# p2sdc-001.net
KiCad netlist of a schematic drawn in EAGLE
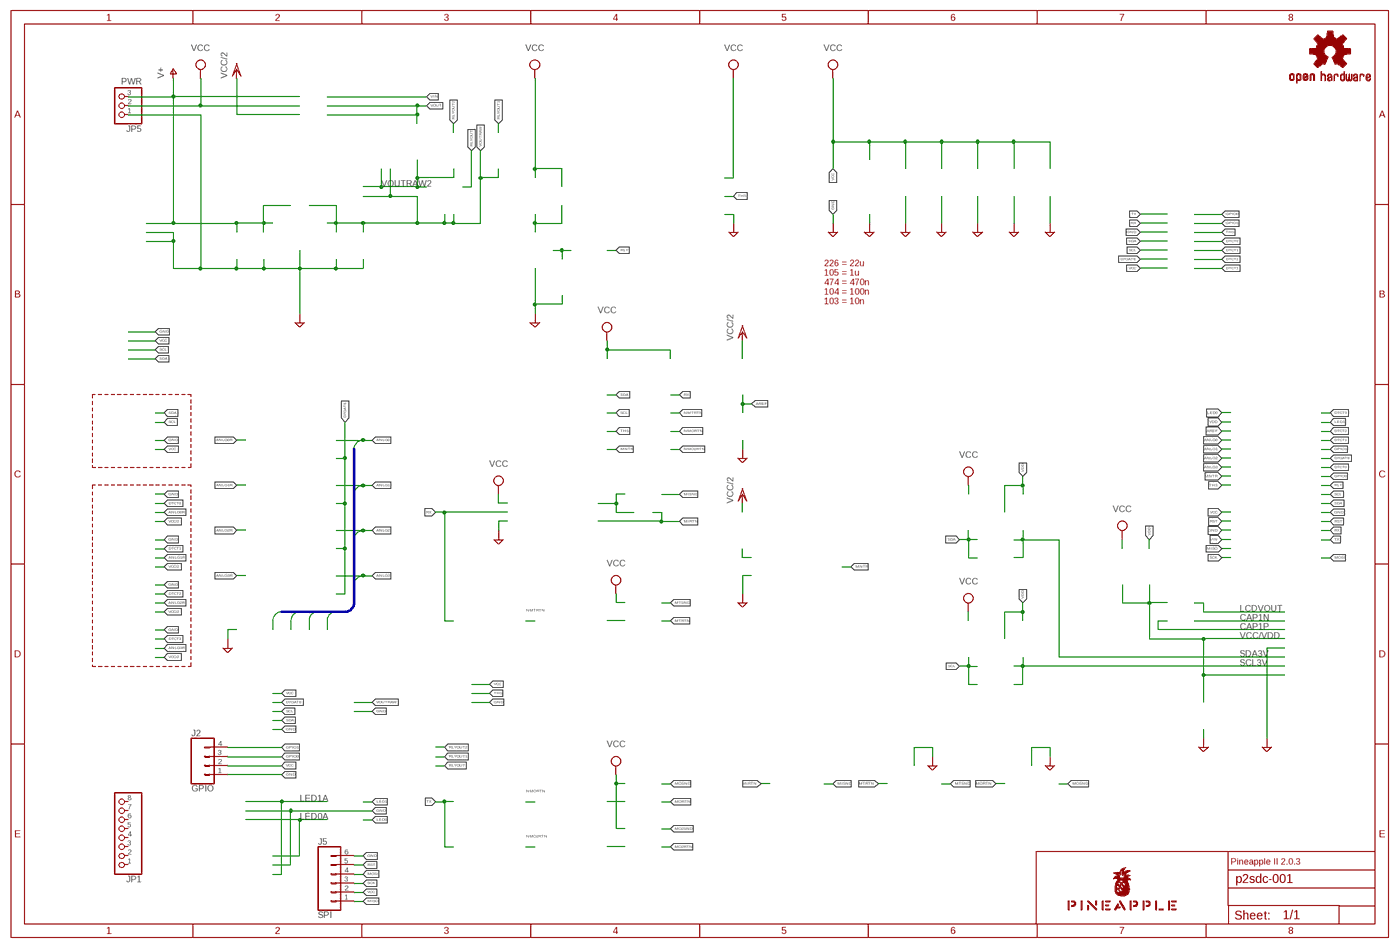
[diagram p0: schematic, sheet 1, overview]
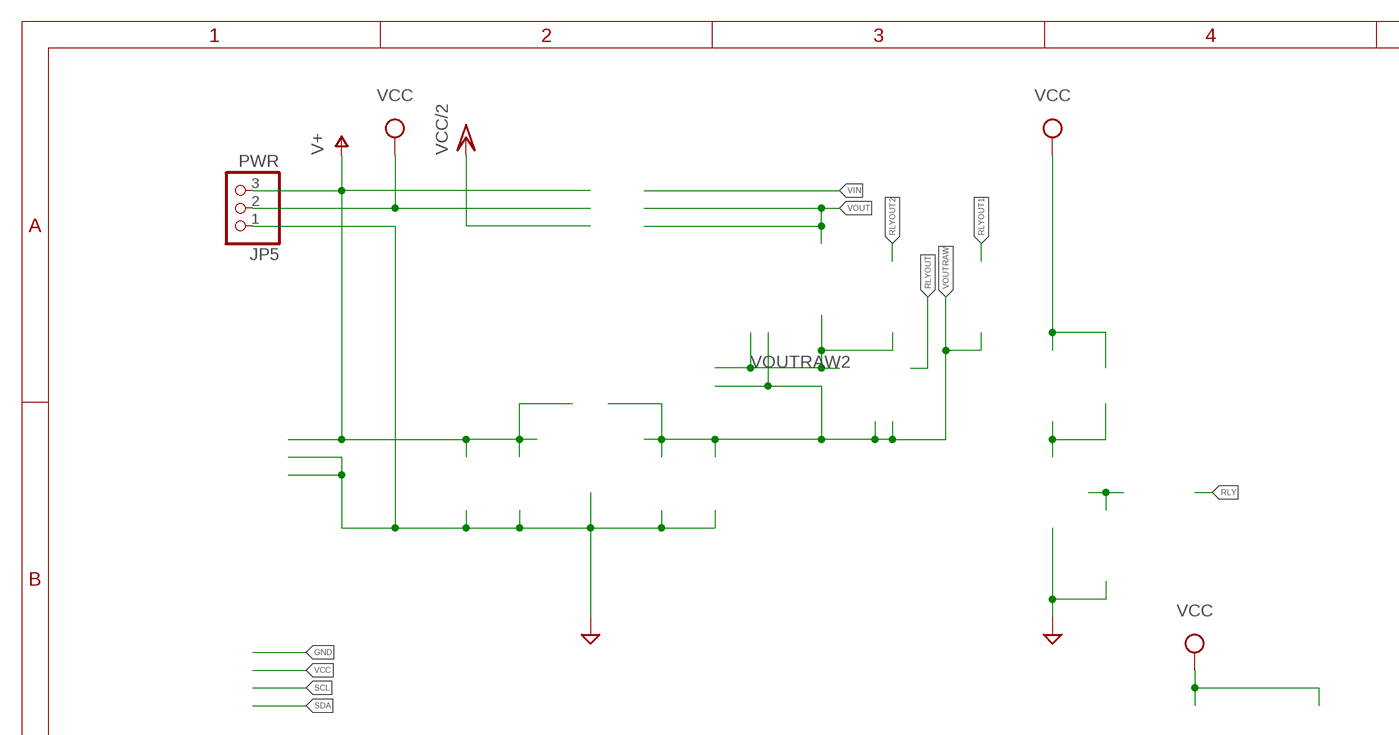
[diagram p1: schematic, sheet 1, part 1 of 4]
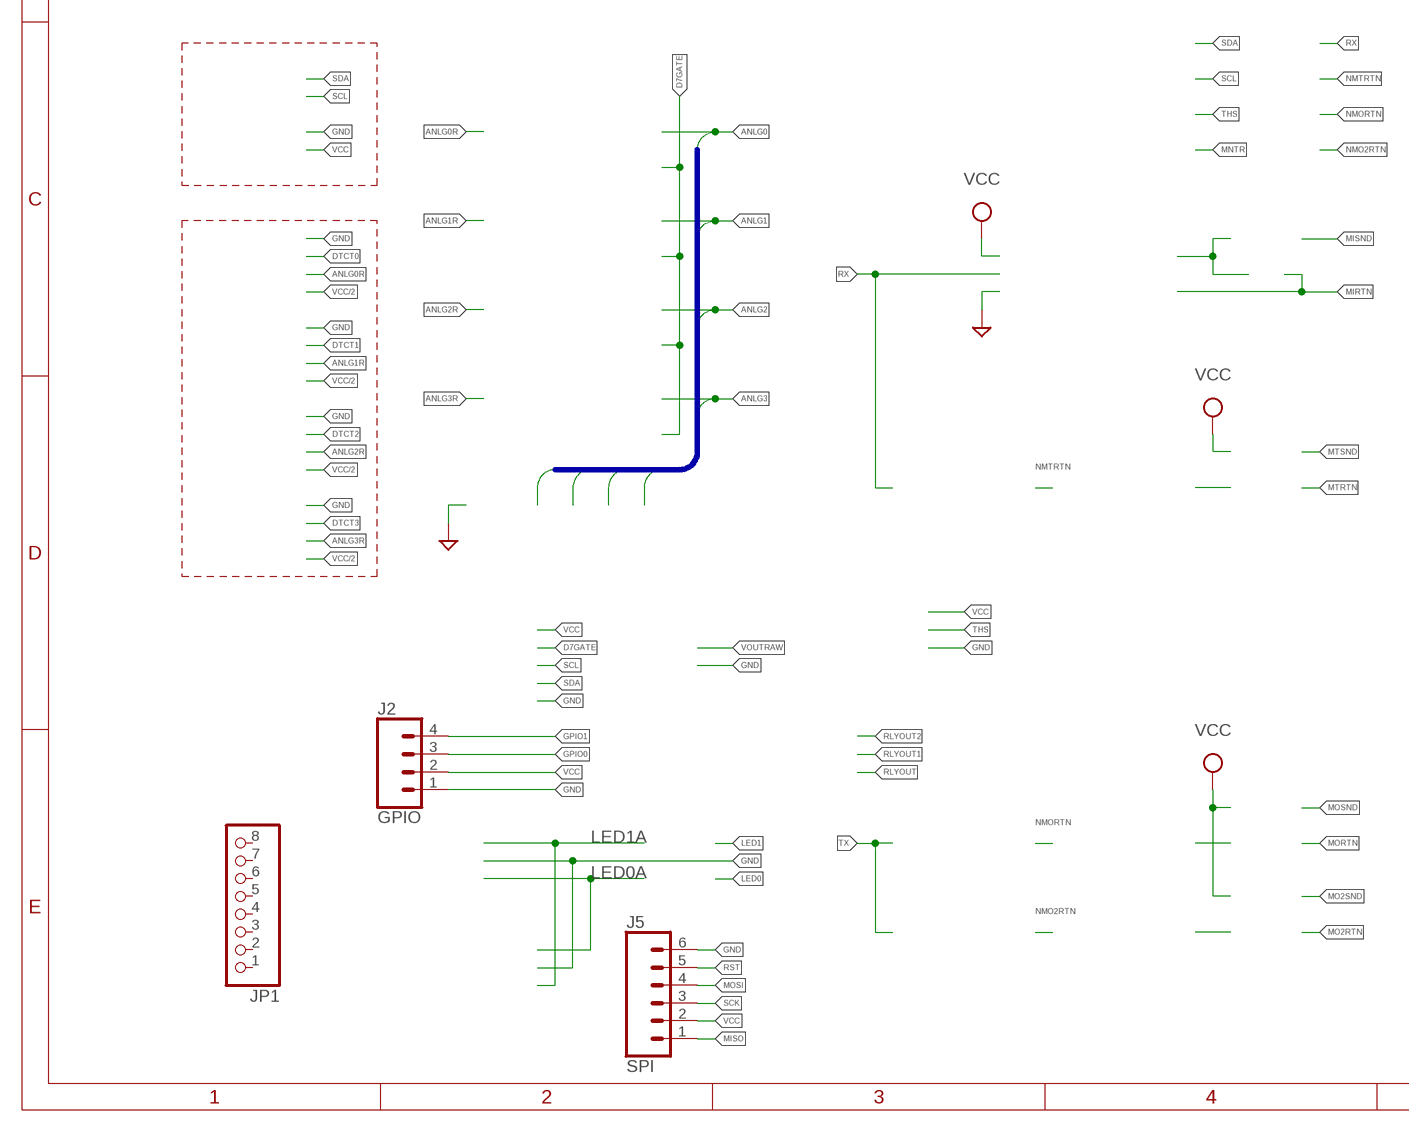
[diagram p2: schematic, sheet 1, part 2 of 4]
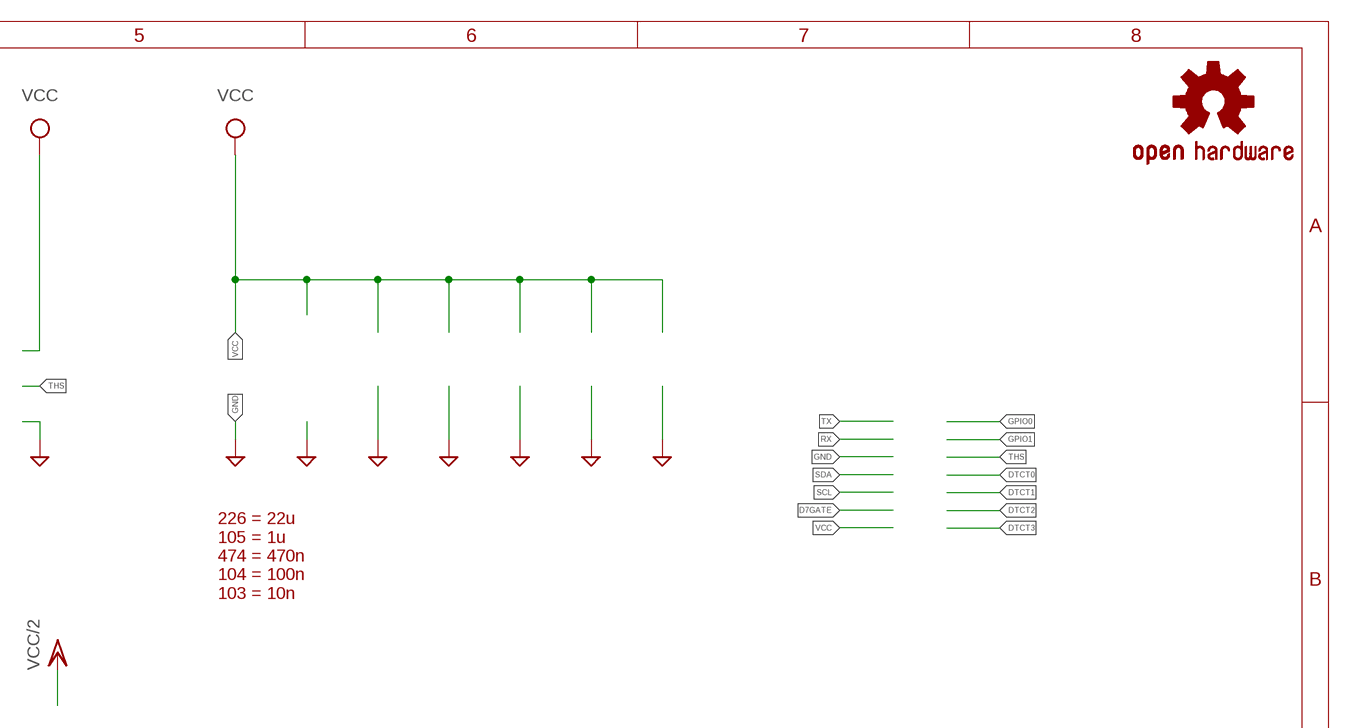
[diagram p3: schematic, sheet 1, part 3 of 4]
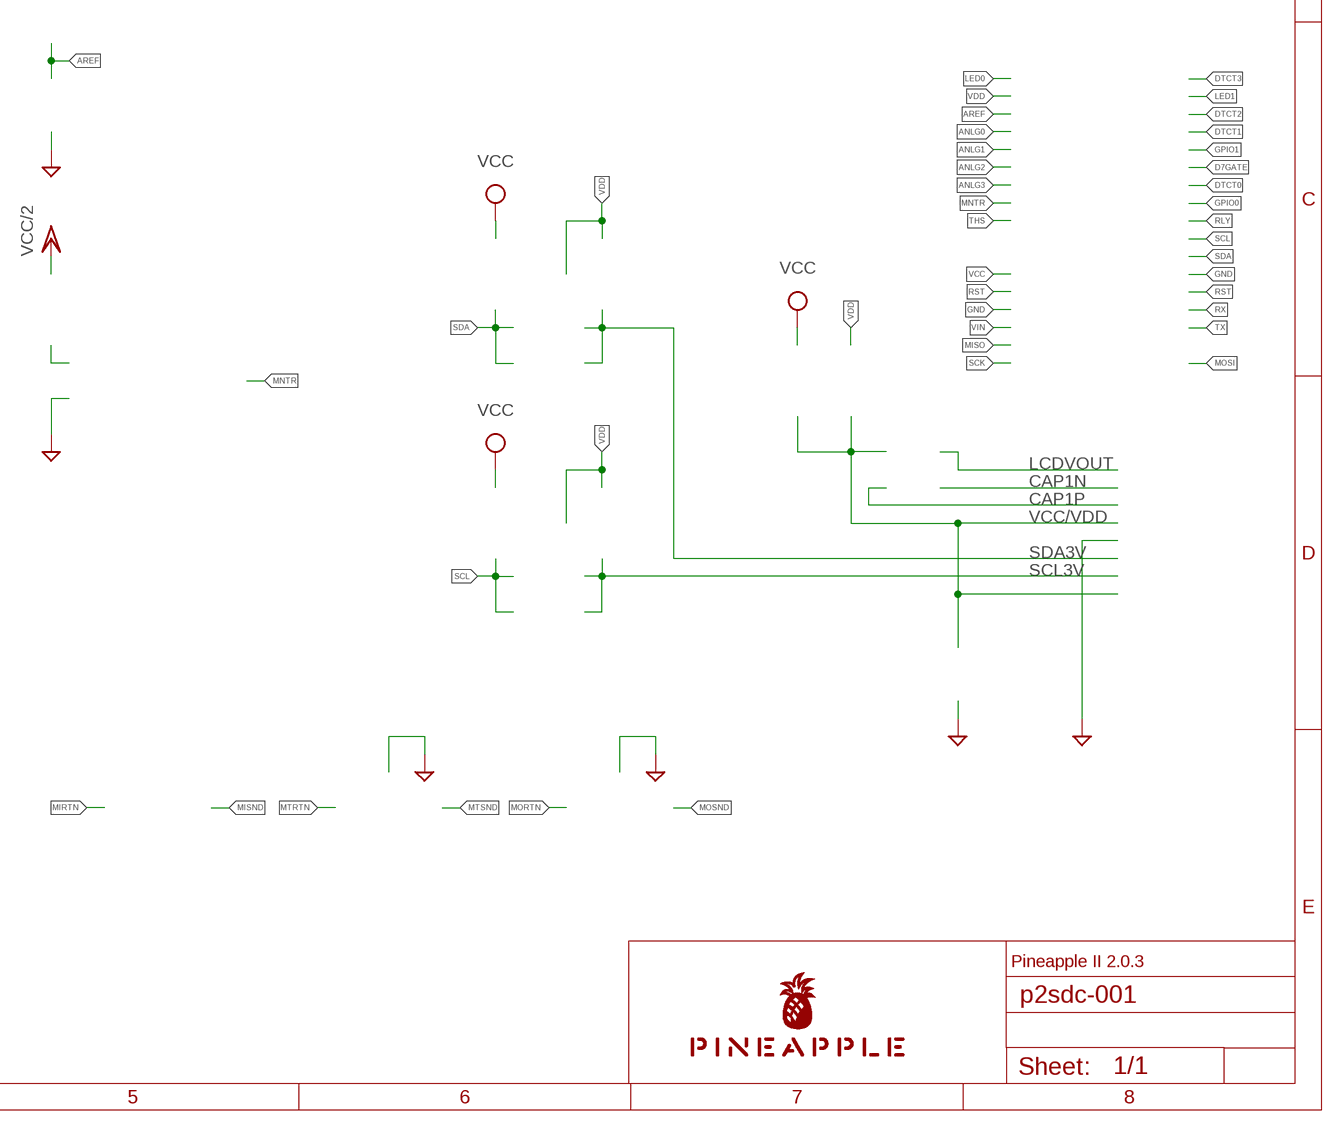
[diagram p4: schematic, sheet 1, part 4 of 4]

(export (version "E")
  (design (tool "Eeschema 10.0.6"))
  (components
    (comp (ref "J2")
      (value "GPIO")
      (footprint "eagle-import:JST-4-PTH")
      (libsource (lib "eagle-import") (part "CONN_04JST-PTH"))
    )
    (comp (ref "J5")
      (value "SPI")
      (footprint "eagle-import:1X06_1.27MM")
      (libsource (lib "eagle-import") (part "CONN_061.27MM"))
    )
    (comp (ref "JP1")
      (value "PINHD-1X8")
      (footprint "eagle-import:1X08")
      (libsource (lib "eagle-import") (part "PINHD-1X8"))
    )
    (comp (ref "JP5")
      (value "PWR")
      (footprint "eagle-import:1X03")
      (libsource (lib "eagle-import") (part "PINHD-1X3"))
    )
    (comp (ref "LOGO1")
      (value "OSHW-LOGOS-COPPER")
      (footprint "eagle-import:OSHW-LOGO-S_COPPER")
      (libsource (lib "eagle-import") (part "OSHW-LOGOS-COPPER"))
    )
    (comp (ref "U$1")
      (value "PINEAPPLE450_SILK")
      (footprint "eagle-import:PINEAPPLE450_SILK")
      (libsource (lib "eagle-import") (part "PINEAPPLE450_SILK"))
    )
  )
  (nets
    (net (code "24") (name "GND") (class "Default")
      (node (ref "J2") (pin "1") (pinfunction "1_1") (pintype "passive"))
      (node (ref "J5") (pin "6") (pinfunction "6_6") (pintype "passive"))
      (node (ref "JP5") (pin "1") (pinfunction "1_1") (pintype "passive"))
    )
    (net (code "25") (name "GPIO0") (class "Default")
      (node (ref "J2") (pin "3") (pinfunction "3_3") (pintype "passive"))
    )
    (net (code "26") (name "GPIO1") (class "Default")
      (node (ref "J2") (pin "4") (pinfunction "4_4") (pintype "passive"))
    )
    (net (code "31") (name "MISO") (class "Default")
      (node (ref "J5") (pin "1") (pinfunction "1_1") (pintype "passive"))
    )
    (net (code "36") (name "MOSI") (class "Default")
      (node (ref "J5") (pin "4") (pinfunction "4_4") (pintype "passive"))
    )
    (net (code "47") (name "RST") (class "Default")
      (node (ref "J5") (pin "5") (pinfunction "5_5") (pintype "passive"))
    )
    (net (code "49") (name "SCK") (class "Default")
      (node (ref "J5") (pin "3") (pinfunction "3_3") (pintype "passive"))
    )
    (net (code "54") (name "V+") (class "Default")
      (node (ref "JP5") (pin "3") (pinfunction "3_3") (pintype "passive"))
    )
    (net (code "55") (name "VCC") (class "Default")
      (node (ref "J2") (pin "2") (pinfunction "2_2") (pintype "passive"))
      (node (ref "J5") (pin "2") (pinfunction "2_2") (pintype "passive"))
      (node (ref "JP5") (pin "2") (pinfunction "2_2") (pintype "passive"))
    )
    (net (code "61") (name "unconnected-(JP1-Pad1)") (class "Default")
      (node (ref "JP1") (pin "1") (pinfunction "1_1") (pintype "passive"))
    )
    (net (code "62") (name "unconnected-(JP1-Pad2)") (class "Default")
      (node (ref "JP1") (pin "2") (pinfunction "2_2") (pintype "passive"))
    )
    (net (code "63") (name "unconnected-(JP1-Pad3)") (class "Default")
      (node (ref "JP1") (pin "3") (pinfunction "3_3") (pintype "passive"))
    )
    (net (code "64") (name "unconnected-(JP1-Pad4)") (class "Default")
      (node (ref "JP1") (pin "4") (pinfunction "4_4") (pintype "passive"))
    )
    (net (code "65") (name "unconnected-(JP1-Pad5)") (class "Default")
      (node (ref "JP1") (pin "5") (pinfunction "5_5") (pintype "passive"))
    )
    (net (code "66") (name "unconnected-(JP1-Pad6)") (class "Default")
      (node (ref "JP1") (pin "6") (pinfunction "6_6") (pintype "passive"))
    )
    (net (code "67") (name "unconnected-(JP1-Pad7)") (class "Default")
      (node (ref "JP1") (pin "7") (pinfunction "7_7") (pintype "passive"))
    )
    (net (code "68") (name "unconnected-(JP1-Pad8)") (class "Default")
      (node (ref "JP1") (pin "8") (pinfunction "8_8") (pintype "passive"))
    )
  )
)
